# Cymru_55.net
KiCad netlist of a schematic drawn in EAGLE
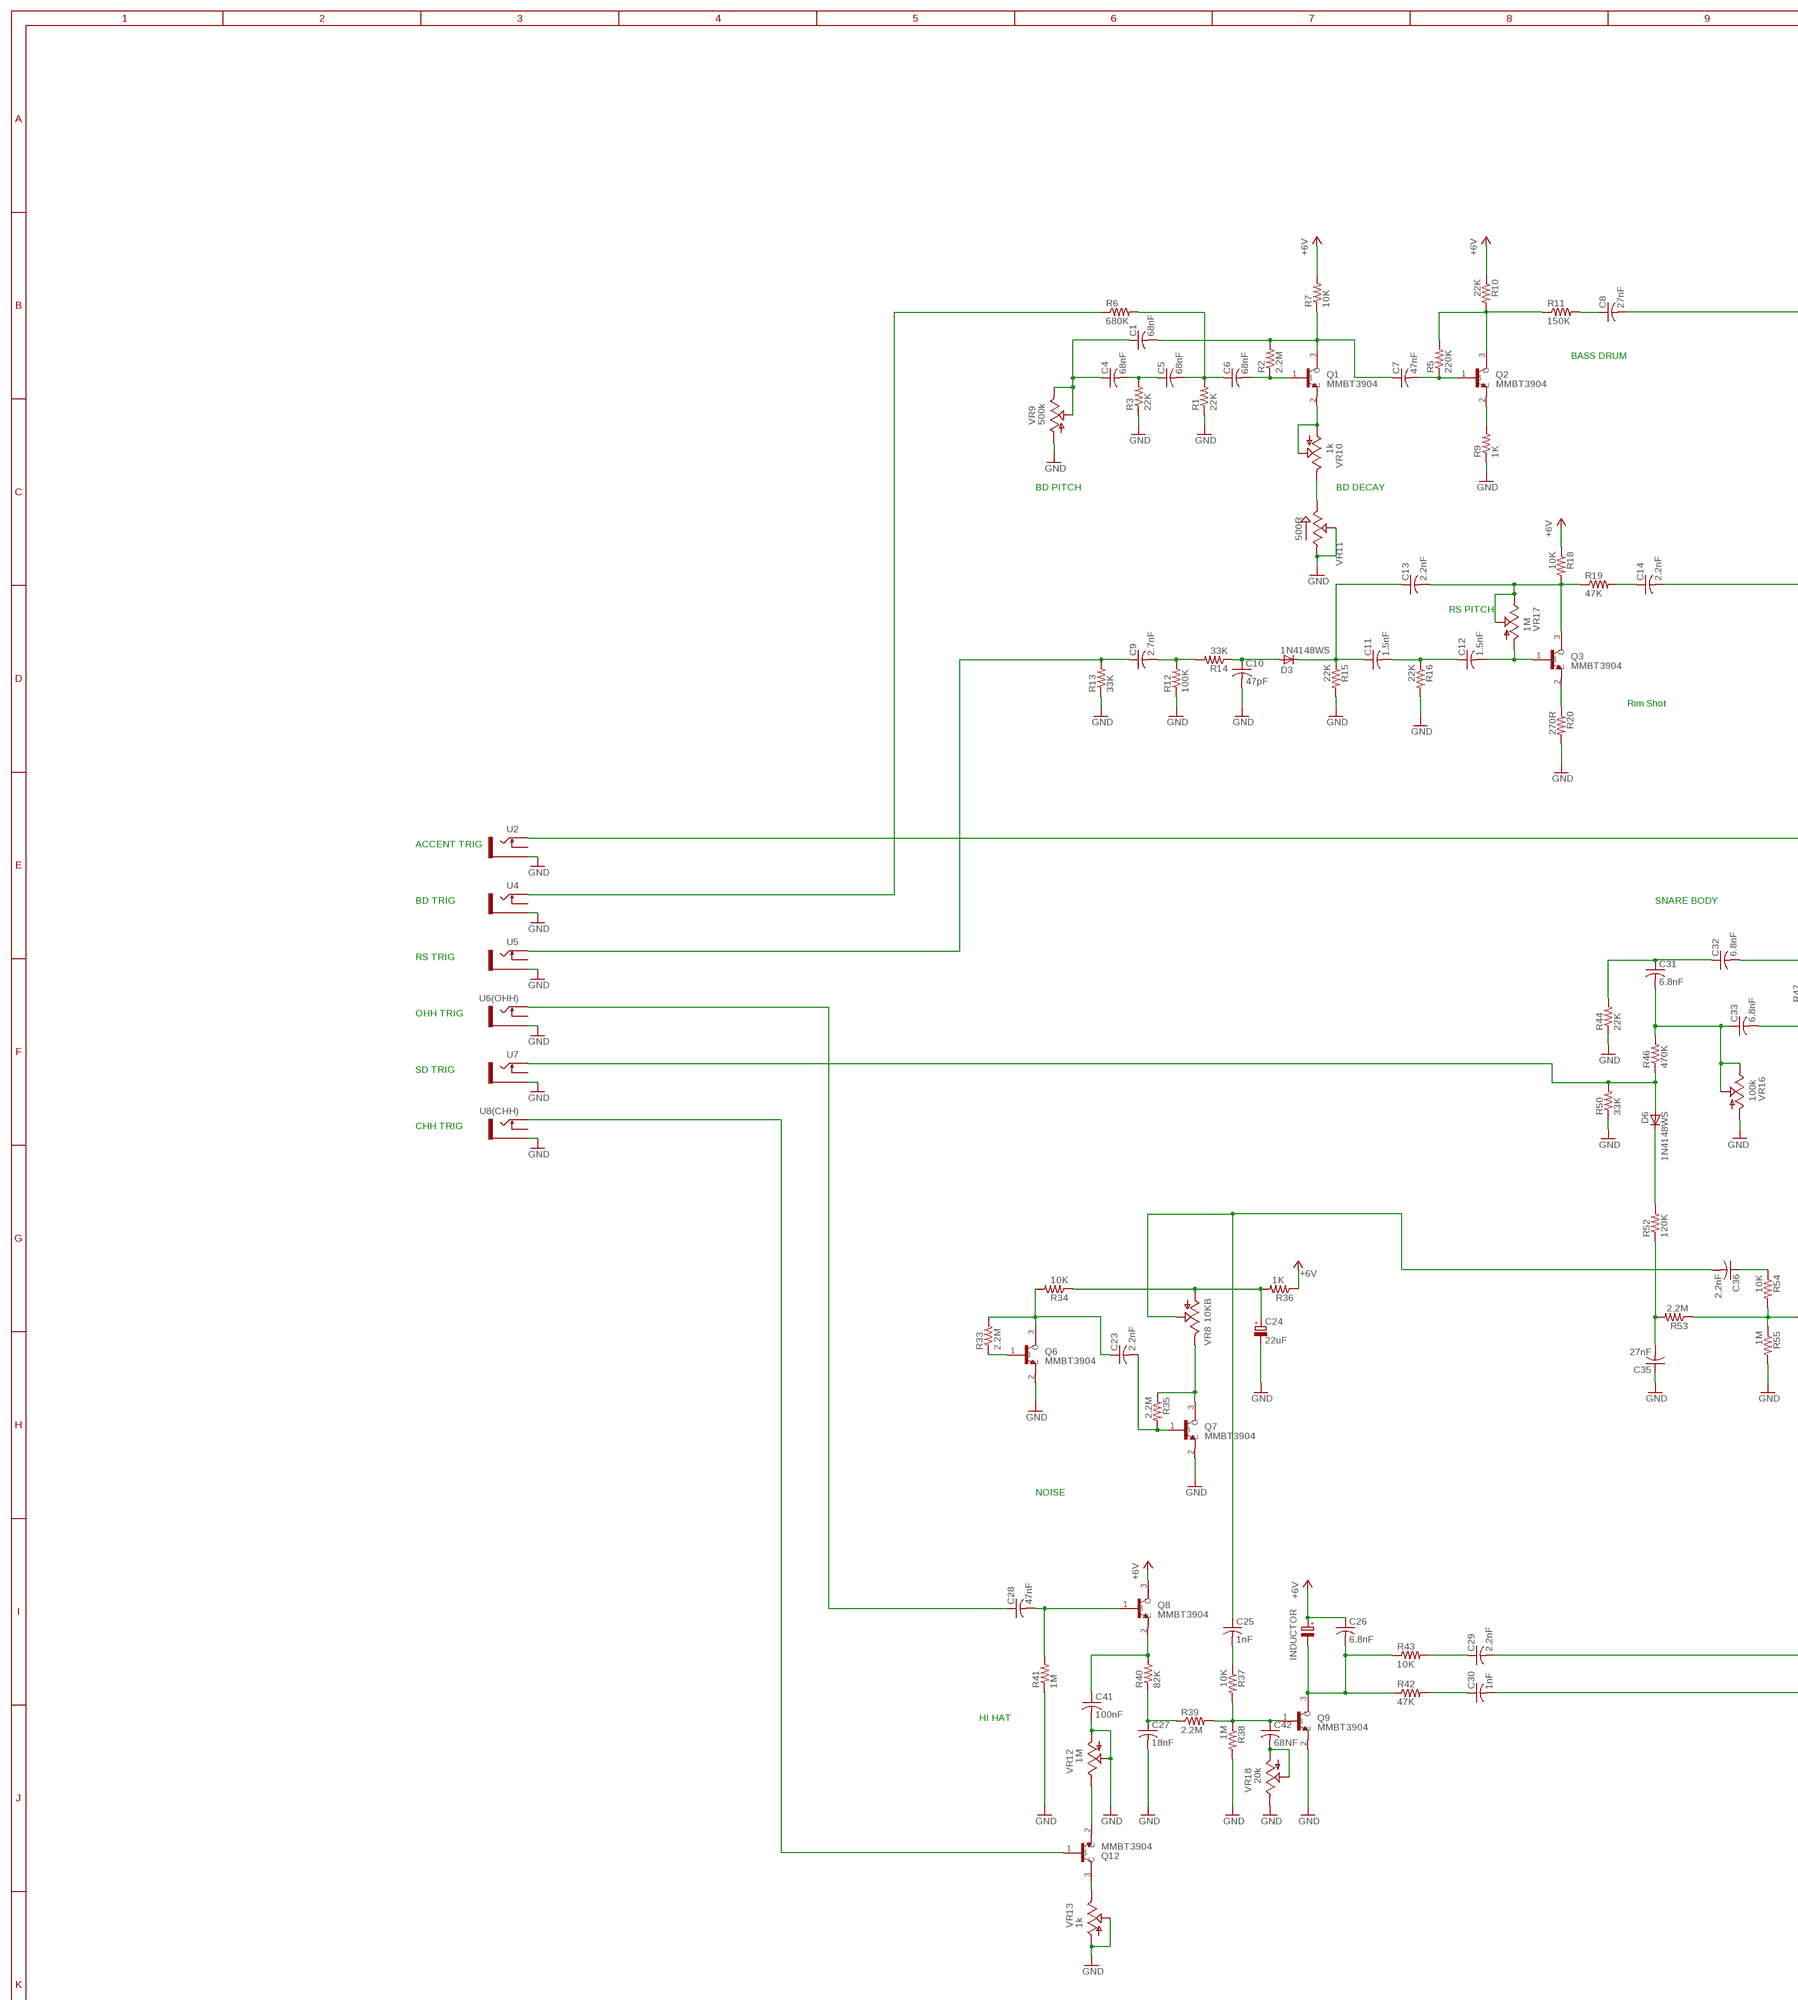
[diagram p0: schematic, sheet 1, part 1 of 3]
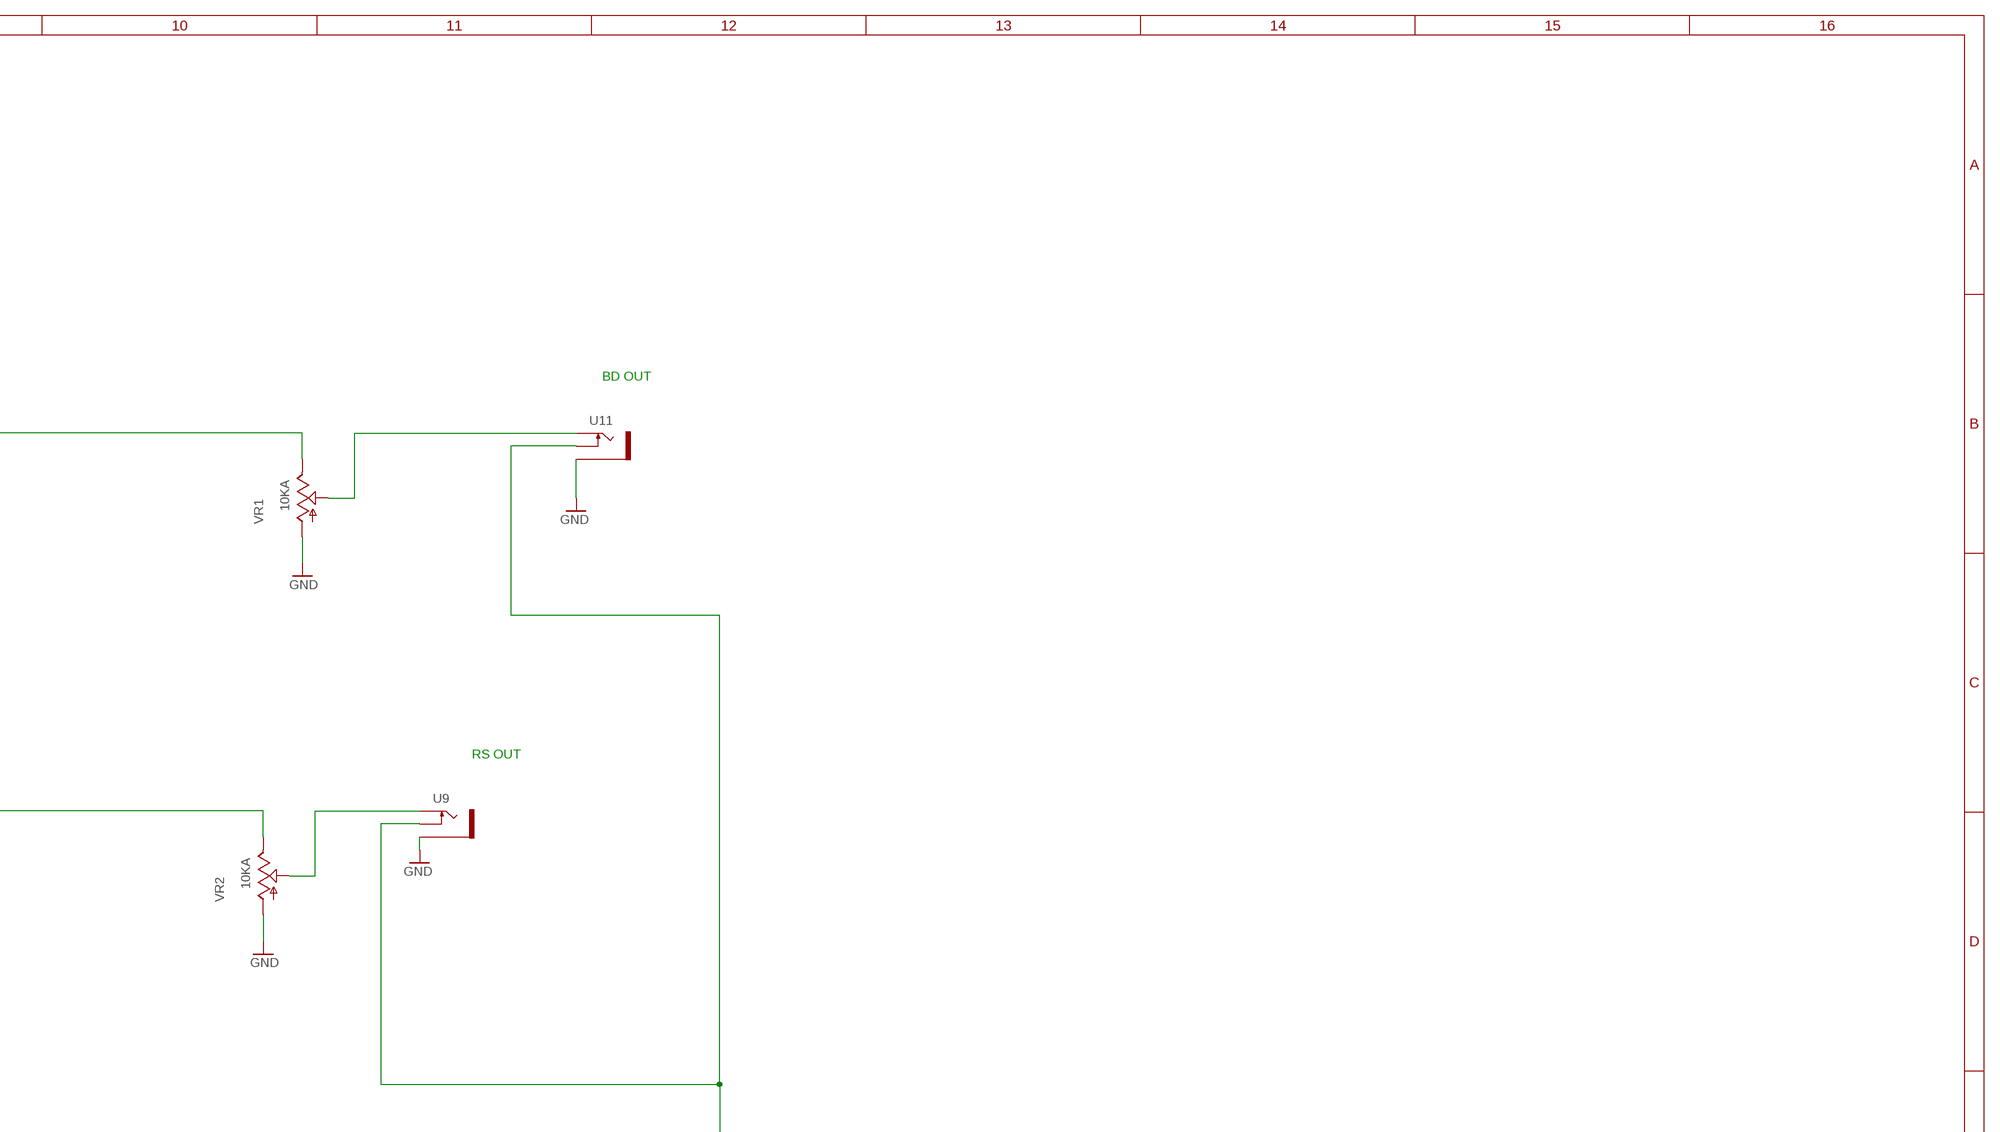
[diagram p1: schematic, sheet 1, part 2 of 3]
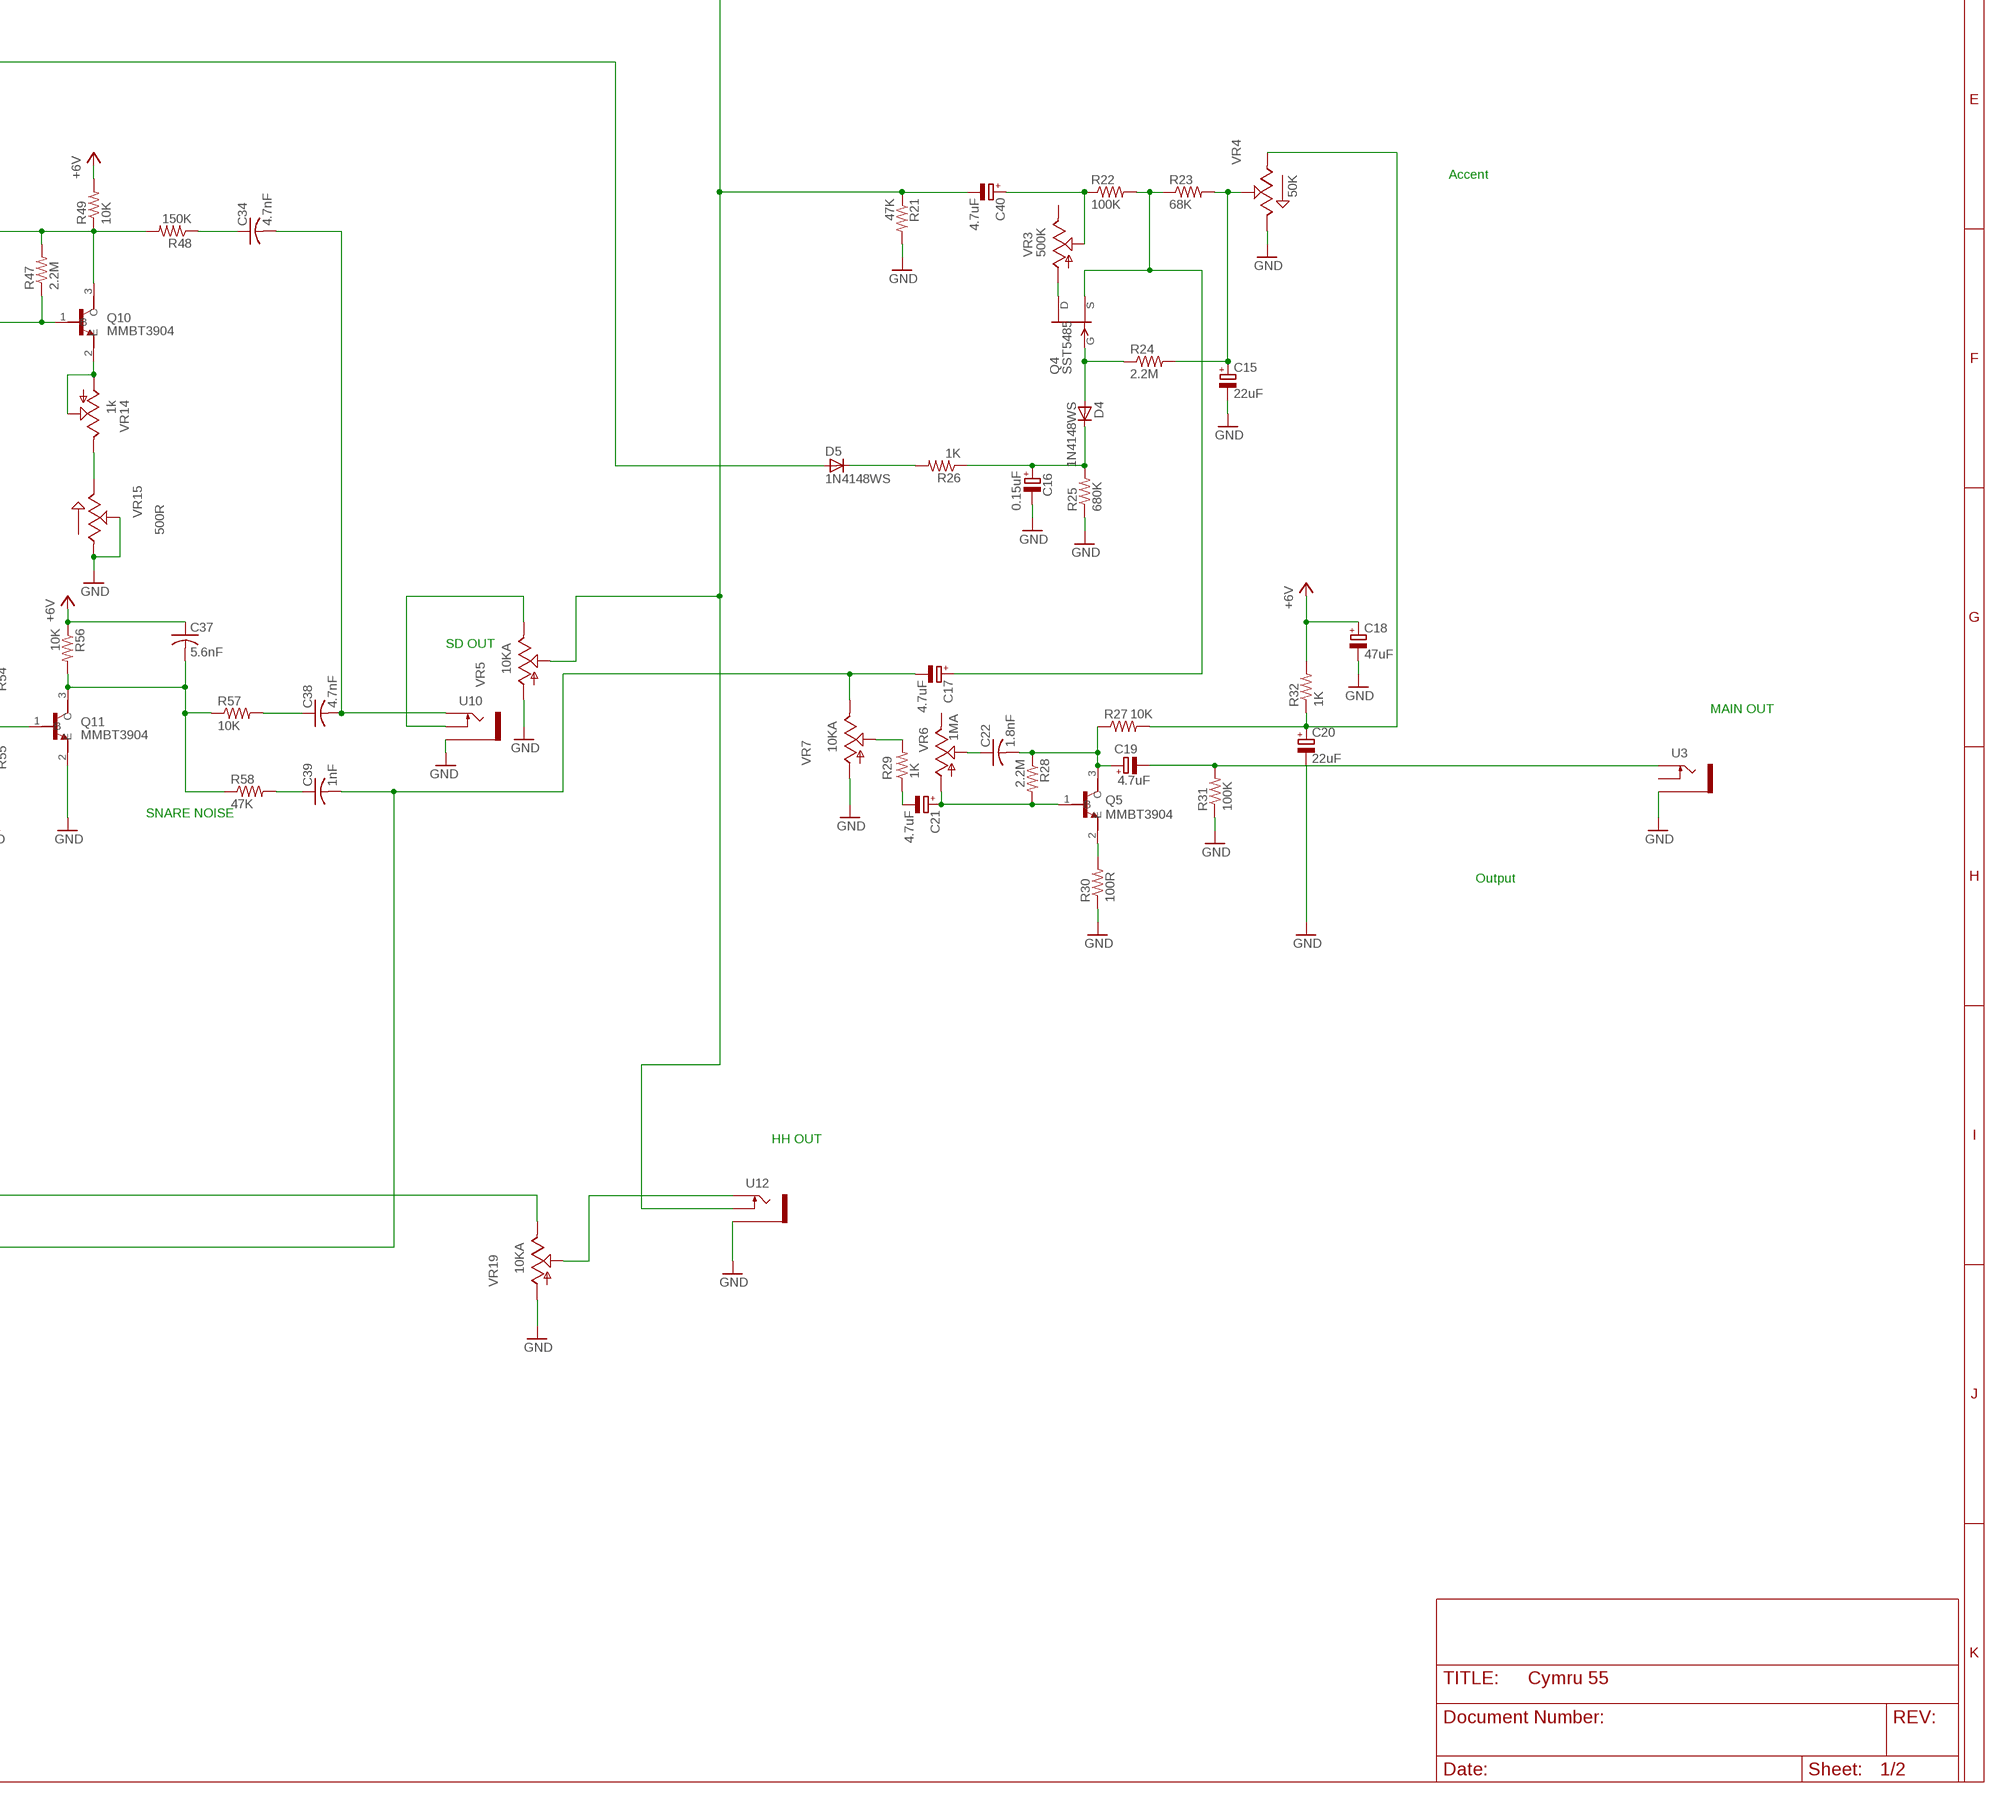
[diagram p2: schematic, sheet 1, part 3 of 3]
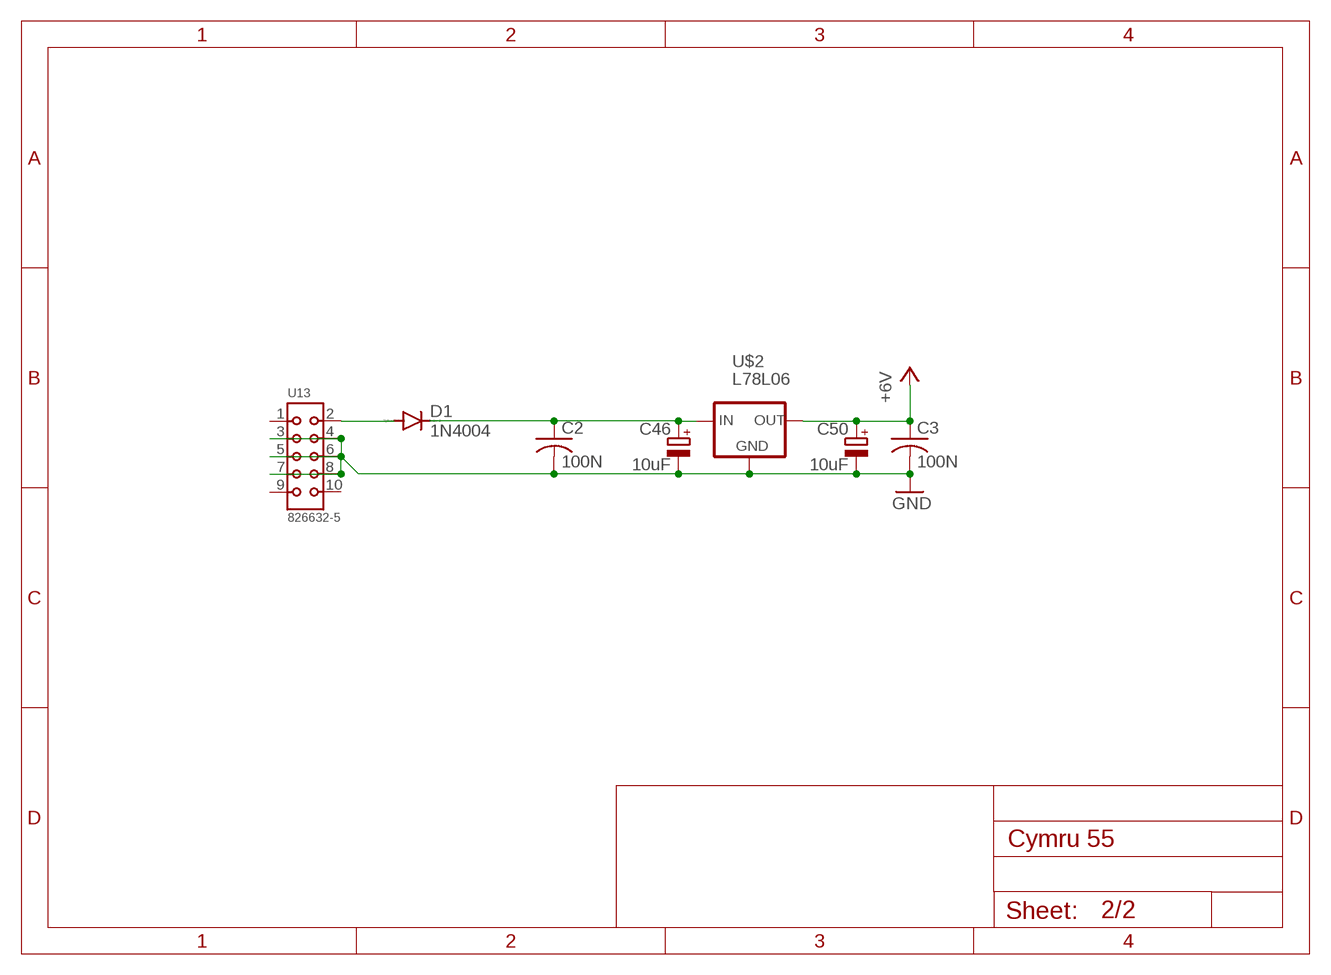
[diagram p3: schematic, sheet 2]

(export (version "E")
  (design (tool "Eeschema 10.0.6"))
  (components
    (comp (ref "C1")
      (value "68nF")
      (footprint "eagle-import:C0603")
      (libsource (lib "eagle-import") (part "C-USC0603"))
    )
    (comp (ref "C4")
      (value "68nF")
      (footprint "eagle-import:C0603")
      (libsource (lib "eagle-import") (part "C-USC0603"))
    )
    (comp (ref "C5")
      (value "68nF")
      (footprint "eagle-import:C0603")
      (libsource (lib "eagle-import") (part "C-USC0603"))
    )
    (comp (ref "C6")
      (value "68nF")
      (footprint "eagle-import:C0603")
      (libsource (lib "eagle-import") (part "C-USC0603"))
    )
    (comp (ref "C7")
      (value "47nF")
      (footprint "eagle-import:C0603")
      (libsource (lib "eagle-import") (part "C-USC0603"))
    )
    (comp (ref "C8")
      (value "27nF")
      (footprint "eagle-import:C0603")
      (libsource (lib "eagle-import") (part "C-USC0603"))
    )
    (comp (ref "C9")
      (value "2.7nF")
      (footprint "eagle-import:C0603")
      (libsource (lib "eagle-import") (part "C-USC0603"))
    )
    (comp (ref "C10")
      (value "47pF")
      (footprint "eagle-import:C0603")
      (libsource (lib "eagle-import") (part "C-USC0603"))
    )
    (comp (ref "C11")
      (value "1.5nF")
      (footprint "eagle-import:C0603")
      (libsource (lib "eagle-import") (part "C-USC0603"))
    )
    (comp (ref "C12")
      (value "1.5nF")
      (footprint "eagle-import:C0603")
      (libsource (lib "eagle-import") (part "C-USC0603"))
    )
    (comp (ref "C13")
      (value "2.2nF")
      (footprint "eagle-import:C0603")
      (libsource (lib "eagle-import") (part "C-USC0603"))
    )
    (comp (ref "C14")
      (value "2.2nF")
      (footprint "eagle-import:C0603")
      (libsource (lib "eagle-import") (part "C-USC0603"))
    )
    (comp (ref "C15")
      (value "22uF")
      (footprint "eagle-import:E2,5RE")
      (libsource (lib "eagle-import") (part "CPOL-EUE2.5-4V"))
    )
    (comp (ref "C16")
      (value "0.15uF")
      (footprint "eagle-import:E2,5RE")
      (libsource (lib "eagle-import") (part "CPOL-EUE2.5-4V"))
    )
    (comp (ref "C17")
      (value "4.7uF")
      (footprint "eagle-import:E2,5RE")
      (libsource (lib "eagle-import") (part "CPOL-EUE2.5-4V"))
    )
    (comp (ref "C18")
      (value "47uF")
      (footprint "eagle-import:E2,5RE")
      (libsource (lib "eagle-import") (part "CPOL-EUE2.5-4V"))
    )
    (comp (ref "C19")
      (value "4.7uF")
      (footprint "eagle-import:E2,5RE")
      (libsource (lib "eagle-import") (part "CPOL-EUE2.5-4V"))
    )
    (comp (ref "C20")
      (value "22uF")
      (footprint "eagle-import:E2,5RE")
      (libsource (lib "eagle-import") (part "CPOL-EUE2.5-4V"))
    )
    (comp (ref "C21")
      (value "4.7uF")
      (footprint "eagle-import:E2,5RE")
      (libsource (lib "eagle-import") (part "CPOL-EUE2.5-4V"))
    )
    (comp (ref "C22")
      (value "1.8nF")
      (footprint "eagle-import:C0603")
      (libsource (lib "eagle-import") (part "C-USC0603"))
    )
    (comp (ref "C23")
      (value "2.2nF")
      (footprint "eagle-import:C0603")
      (libsource (lib "eagle-import") (part "C-USC0603"))
    )
    (comp (ref "C24")
      (value "22uF")
      (footprint "eagle-import:E2,5RE")
      (libsource (lib "eagle-import") (part "CPOL-EUE2.5-4V"))
    )
    (comp (ref "C25")
      (value "1nF")
      (footprint "eagle-import:C0603")
      (libsource (lib "eagle-import") (part "C-USC0603"))
    )
    (comp (ref "C26")
      (value "6.8nF")
      (footprint "eagle-import:C0603")
      (libsource (lib "eagle-import") (part "C-USC0603"))
    )
    (comp (ref "C27")
      (value "18nF")
      (footprint "eagle-import:C0603")
      (libsource (lib "eagle-import") (part "C-USC0603"))
    )
    (comp (ref "C28")
      (value "47nF")
      (footprint "eagle-import:C0603")
      (libsource (lib "eagle-import") (part "C-USC0603"))
    )
    (comp (ref "C29")
      (value "2.2nF")
      (footprint "eagle-import:C0603")
      (libsource (lib "eagle-import") (part "C-USC0603"))
    )
    (comp (ref "C30")
      (value "1nF")
      (footprint "eagle-import:C0603")
      (libsource (lib "eagle-import") (part "C-USC0603"))
    )
    (comp (ref "C31")
      (value "6.8nF")
      (footprint "eagle-import:C0603")
      (libsource (lib "eagle-import") (part "C-USC0603"))
    )
    (comp (ref "C32")
      (value "6.8nF")
      (footprint "eagle-import:C0603")
      (libsource (lib "eagle-import") (part "C-USC0603"))
    )
    (comp (ref "C33")
      (value "6.8nF")
      (footprint "eagle-import:C0603")
      (libsource (lib "eagle-import") (part "C-USC0603"))
    )
    (comp (ref "C34")
      (value "4.7nF")
      (footprint "eagle-import:C0603")
      (libsource (lib "eagle-import") (part "C-USC0603"))
    )
    (comp (ref "C35")
      (value "27nF")
      (footprint "eagle-import:C0603")
      (libsource (lib "eagle-import") (part "C-USC0603"))
    )
    (comp (ref "C36")
      (value "2.2nF")
      (footprint "eagle-import:C0603")
      (libsource (lib "eagle-import") (part "C-USC0603"))
    )
    (comp (ref "C37")
      (value "5.6nF")
      (footprint "eagle-import:C0603")
      (libsource (lib "eagle-import") (part "C-USC0603"))
    )
    (comp (ref "C38")
      (value "4.7nF")
      (footprint "eagle-import:C0603")
      (libsource (lib "eagle-import") (part "C-USC0603"))
    )
    (comp (ref "C39")
      (value "1nF")
      (footprint "eagle-import:C0603")
      (libsource (lib "eagle-import") (part "C-USC0603"))
    )
    (comp (ref "C40")
      (value "4.7uF")
      (footprint "eagle-import:E2,5RE")
      (libsource (lib "eagle-import") (part "CPOL-EUE2.5-4V"))
    )
    (comp (ref "C41")
      (value "100nF")
      (footprint "eagle-import:C0603")
      (libsource (lib "eagle-import") (part "C-USC0603"))
    )
    (comp (ref "C42")
      (value "68NF")
      (footprint "eagle-import:C0603")
      (libsource (lib "eagle-import") (part "C-USC0603"))
    )
    (comp (ref "D3")
      (value "1N4148WS")
      (footprint "eagle-import:SOD323")
      (fields (field (name "MF") "ON Semiconductor"))
      (libsource (lib "eagle-import") (part "1N4148WS"))
    )
    (comp (ref "D4")
      (value "1N4148WS")
      (footprint "eagle-import:SOD323")
      (fields (field (name "MF") "ON Semiconductor"))
      (libsource (lib "eagle-import") (part "1N4148WS"))
    )
    (comp (ref "D5")
      (value "1N4148WS")
      (footprint "eagle-import:SOD323")
      (fields (field (name "MF") "ON Semiconductor"))
      (libsource (lib "eagle-import") (part "1N4148WS"))
    )
    (comp (ref "D6")
      (value "1N4148WS")
      (footprint "eagle-import:SOD323")
      (fields (field (name "MF") "ON Semiconductor"))
      (libsource (lib "eagle-import") (part "1N4148WS"))
    )
    (comp (ref "INDUCTOR")
      (value "47MH")
      (footprint "eagle-import:E2,5RE")
      (libsource (lib "eagle-import") (part "CPOL-EUE2.5-4V"))
    )
    (comp (ref "Q1")
      (value "MMBT3904")
      (footprint "eagle-import:SOT95P240X120-3N")
      (fields (field (name "MF") "STMicroelectronics"))
      (libsource (lib "eagle-import") (part "MMBT3904"))
    )
    (comp (ref "Q2")
      (value "MMBT3904")
      (footprint "eagle-import:SOT95P240X120-3N")
      (fields (field (name "MF") "STMicroelectronics"))
      (libsource (lib "eagle-import") (part "MMBT3904"))
    )
    (comp (ref "Q3")
      (value "MMBT3904")
      (footprint "eagle-import:SOT95P240X120-3N")
      (fields (field (name "MF") "STMicroelectronics"))
      (libsource (lib "eagle-import") (part "MMBT3904"))
    )
    (comp (ref "Q4")
      (value "SST5485")
      (footprint "eagle-import:SOT23")
      (libsource (lib "eagle-import") (part "?548SST5"))
    )
    (comp (ref "Q5")
      (value "MMBT3904")
      (footprint "eagle-import:SOT95P240X120-3N")
      (fields (field (name "MF") "STMicroelectronics"))
      (libsource (lib "eagle-import") (part "MMBT3904"))
    )
    (comp (ref "Q6")
      (value "MMBT3904")
      (footprint "eagle-import:SOT95P240X120-3N")
      (fields (field (name "MF") "STMicroelectronics"))
      (libsource (lib "eagle-import") (part "MMBT3904"))
    )
    (comp (ref "Q7")
      (value "MMBT3904")
      (footprint "eagle-import:SOT95P240X120-3N")
      (fields (field (name "MF") "STMicroelectronics"))
      (libsource (lib "eagle-import") (part "MMBT3904"))
    )
    (comp (ref "Q8")
      (value "MMBT3904")
      (footprint "eagle-import:SOT95P240X120-3N")
      (fields (field (name "MF") "STMicroelectronics"))
      (libsource (lib "eagle-import") (part "MMBT3904"))
    )
    (comp (ref "Q9")
      (value "MMBT3904")
      (footprint "eagle-import:SOT95P240X120-3N")
      (fields (field (name "MF") "STMicroelectronics"))
      (libsource (lib "eagle-import") (part "MMBT3904"))
    )
    (comp (ref "Q10")
      (value "MMBT3904")
      (footprint "eagle-import:SOT95P240X120-3N")
      (fields (field (name "MF") "STMicroelectronics"))
      (libsource (lib "eagle-import") (part "MMBT3904"))
    )
    (comp (ref "Q11")
      (value "MMBT3904")
      (footprint "eagle-import:SOT95P240X120-3N")
      (fields (field (name "MF") "STMicroelectronics"))
      (libsource (lib "eagle-import") (part "MMBT3904"))
    )
    (comp (ref "Q12")
      (value "MMBT3904")
      (footprint "eagle-import:SOT95P240X120-3N")
      (fields (field (name "MF") "STMicroelectronics"))
      (libsource (lib "eagle-import") (part "MMBT3904"))
    )
    (comp (ref "R1")
      (value "22K")
      (footprint "eagle-import:R0603")
      (libsource (lib "eagle-import") (part "R-US_R0603"))
    )
    (comp (ref "R2")
      (value "2.2M")
      (footprint "eagle-import:R0603")
      (libsource (lib "eagle-import") (part "R-US_R0603"))
    )
    (comp (ref "R3")
      (value "22K")
      (footprint "eagle-import:R0603")
      (libsource (lib "eagle-import") (part "R-US_R0603"))
    )
    (comp (ref "R5")
      (value "220K")
      (footprint "eagle-import:R0603")
      (libsource (lib "eagle-import") (part "R-US_R0603"))
    )
    (comp (ref "R6")
      (value "680K")
      (footprint "eagle-import:R0603")
      (libsource (lib "eagle-import") (part "R-US_R0603"))
    )
    (comp (ref "R7")
      (value "10K")
      (footprint "eagle-import:R0603")
      (libsource (lib "eagle-import") (part "R-US_R0603"))
    )
    (comp (ref "R9")
      (value "1K")
      (footprint "eagle-import:R0603")
      (libsource (lib "eagle-import") (part "R-US_R0603"))
    )
    (comp (ref "R10")
      (value "22K")
      (footprint "eagle-import:R0603")
      (libsource (lib "eagle-import") (part "R-US_R0603"))
    )
    (comp (ref "R11")
      (value "150K")
      (footprint "eagle-import:R0603")
      (libsource (lib "eagle-import") (part "R-US_R0603"))
    )
    (comp (ref "R12")
      (value "100K")
      (footprint "eagle-import:R0603")
      (libsource (lib "eagle-import") (part "R-US_R0603"))
    )
    (comp (ref "R13")
      (value "33K")
      (footprint "eagle-import:R0603")
      (libsource (lib "eagle-import") (part "R-US_R0603"))
    )
    (comp (ref "R14")
      (value "33K")
      (footprint "eagle-import:R0603")
      (libsource (lib "eagle-import") (part "R-US_R0603"))
    )
    (comp (ref "R15")
      (value "22K")
      (footprint "eagle-import:R0603")
      (libsource (lib "eagle-import") (part "R-US_R0603"))
    )
    (comp (ref "R16")
      (value "22K")
      (footprint "eagle-import:R0603")
      (libsource (lib "eagle-import") (part "R-US_R0603"))
    )
    (comp (ref "R18")
      (value "10K")
      (footprint "eagle-import:R0603")
      (libsource (lib "eagle-import") (part "R-US_R0603"))
    )
    (comp (ref "R19")
      (value "47K")
      (footprint "eagle-import:R0603")
      (libsource (lib "eagle-import") (part "R-US_R0603"))
    )
    (comp (ref "R20")
      (value "270R")
      (footprint "eagle-import:R0603")
      (libsource (lib "eagle-import") (part "R-US_R0603"))
    )
    (comp (ref "R21")
      (value "47K")
      (footprint "eagle-import:R0603")
      (libsource (lib "eagle-import") (part "R-US_R0603"))
    )
    (comp (ref "R22")
      (value "100K")
      (footprint "eagle-import:R0603")
      (libsource (lib "eagle-import") (part "R-US_R0603"))
    )
    (comp (ref "R23")
      (value "68K")
      (footprint "eagle-import:R0603")
      (libsource (lib "eagle-import") (part "R-US_R0603"))
    )
    (comp (ref "R24")
      (value "2.2M")
      (footprint "eagle-import:R0603")
      (libsource (lib "eagle-import") (part "R-US_R0603"))
    )
    (comp (ref "R25")
      (value "680K")
      (footprint "eagle-import:R0603")
      (libsource (lib "eagle-import") (part "R-US_R0603"))
    )
    (comp (ref "R26")
      (value "1K")
      (footprint "eagle-import:R0603")
      (libsource (lib "eagle-import") (part "R-US_R0603"))
    )
    (comp (ref "R27")
      (value "10K")
      (footprint "eagle-import:R0603")
      (libsource (lib "eagle-import") (part "R-US_R0603"))
    )
    (comp (ref "R28")
      (value "2.2M")
      (footprint "eagle-import:R0603")
      (libsource (lib "eagle-import") (part "R-US_R0603"))
    )
    (comp (ref "R29")
      (value "1K")
      (footprint "eagle-import:R0603")
      (libsource (lib "eagle-import") (part "R-US_R0603"))
    )
    (comp (ref "R30")
      (value "100R")
      (footprint "eagle-import:R0603")
      (libsource (lib "eagle-import") (part "R-US_R0603"))
    )
    (comp (ref "R31")
      (value "100K")
      (footprint "eagle-import:R0603")
      (libsource (lib "eagle-import") (part "R-US_R0603"))
    )
    (comp (ref "R32")
      (value "1K")
      (footprint "eagle-import:R0603")
      (libsource (lib "eagle-import") (part "R-US_R0603"))
    )
    (comp (ref "R33")
      (value "2.2M")
      (footprint "eagle-import:R0603")
      (libsource (lib "eagle-import") (part "R-US_R0603"))
    )
    (comp (ref "R34")
      (value "10K")
      (footprint "eagle-import:R0603")
      (libsource (lib "eagle-import") (part "R-US_R0603"))
    )
    (comp (ref "R35")
      (value "2.2M")
      (footprint "eagle-import:R0603")
      (libsource (lib "eagle-import") (part "R-US_R0603"))
    )
    (comp (ref "R36")
      (value "1K")
      (footprint "eagle-import:R0603")
      (libsource (lib "eagle-import") (part "R-US_R0603"))
    )
    (comp (ref "R37")
      (value "10K")
      (footprint "eagle-import:R0603")
      (libsource (lib "eagle-import") (part "R-US_R0603"))
    )
    (comp (ref "R38")
      (value "1M")
      (footprint "eagle-import:R0603")
      (libsource (lib "eagle-import") (part "R-US_R0603"))
    )
    (comp (ref "R39")
      (value "2.2M")
      (footprint "eagle-import:R0603")
      (libsource (lib "eagle-import") (part "R-US_R0603"))
    )
    (comp (ref "R40")
      (value "82K")
      (footprint "eagle-import:R0603")
      (libsource (lib "eagle-import") (part "R-US_R0603"))
    )
    (comp (ref "R41")
      (value "1M")
      (footprint "eagle-import:R0603")
      (libsource (lib "eagle-import") (part "R-US_R0603"))
    )
    (comp (ref "R42")
      (value "47K")
      (footprint "eagle-import:R0603")
      (libsource (lib "eagle-import") (part "R-US_R0603"))
    )
    (comp (ref "R43")
      (value "10K")
      (footprint "eagle-import:R0603")
      (libsource (lib "eagle-import") (part "R-US_R0603"))
    )
    (comp (ref "R44")
      (value "22K")
      (footprint "eagle-import:R0603")
      (libsource (lib "eagle-import") (part "R-US_R0603"))
    )
    (comp (ref "R46")
      (value "470K")
      (footprint "eagle-import:R0603")
      (libsource (lib "eagle-import") (part "R-US_R0603"))
    )
    (comp (ref "R47")
      (value "2.2M")
      (footprint "eagle-import:R0603")
      (libsource (lib "eagle-import") (part "R-US_R0603"))
    )
    (comp (ref "R48")
      (value "150K")
      (footprint "eagle-import:R0603")
      (libsource (lib "eagle-import") (part "R-US_R0603"))
    )
    (comp (ref "R49")
      (value "10K")
      (footprint "eagle-import:R0603")
      (libsource (lib "eagle-import") (part "R-US_R0603"))
    )
    (comp (ref "R50")
      (value "33K")
      (footprint "eagle-import:R0603")
      (libsource (lib "eagle-import") (part "R-US_R0603"))
    )
    (comp (ref "R52")
      (value "120K")
      (footprint "eagle-import:R0603")
      (libsource (lib "eagle-import") (part "R-US_R0603"))
    )
    (comp (ref "R53")
      (value "2.2M")
      (footprint "eagle-import:R0603")
      (libsource (lib "eagle-import") (part "R-US_R0603"))
    )
    (comp (ref "R54")
      (value "10K")
      (footprint "eagle-import:R0603")
      (libsource (lib "eagle-import") (part "R-US_R0603"))
    )
    (comp (ref "R55")
      (value "1M")
      (footprint "eagle-import:R0603")
      (libsource (lib "eagle-import") (part "R-US_R0603"))
    )
    (comp (ref "R56")
      (value "10K")
      (footprint "eagle-import:R0603")
      (libsource (lib "eagle-import") (part "R-US_R0603"))
    )
    (comp (ref "R57")
      (value "10K")
      (footprint "eagle-import:R0603")
      (libsource (lib "eagle-import") (part "R-US_R0603"))
    )
    (comp (ref "R58")
      (value "47K")
      (footprint "eagle-import:R0603")
      (libsource (lib "eagle-import") (part "R-US_R0603"))
    )
    (comp (ref "U2")
      (value "THONKICONNNEW")
      (footprint "eagle-import:WQP-PJ301M-12_JACK")
      (libsource (lib "eagle-import") (part "THONKICONNNEW"))
    )
    (comp (ref "U3")
      (value "THONKICONNNEW")
      (footprint "eagle-import:WQP-PJ301M-12_JACK")
      (libsource (lib "eagle-import") (part "THONKICONNNEW"))
    )
    (comp (ref "U4")
      (value "THONKICONNNEW")
      (footprint "eagle-import:WQP-PJ301M-12_JACK")
      (libsource (lib "eagle-import") (part "THONKICONNNEW"))
    )
    (comp (ref "U5")
      (value "THONKICONNNEW")
      (footprint "eagle-import:WQP-PJ301M-12_JACK")
      (libsource (lib "eagle-import") (part "THONKICONNNEW"))
    )
    (comp (ref "U6(OHH)")
      (value "THONKICONNNEW")
      (footprint "eagle-import:WQP-PJ301M-12_JACK")
      (libsource (lib "eagle-import") (part "THONKICONNNEW"))
    )
    (comp (ref "U7")
      (value "THONKICONNNEW")
      (footprint "eagle-import:WQP-PJ301M-12_JACK")
      (libsource (lib "eagle-import") (part "THONKICONNNEW"))
    )
    (comp (ref "U8(CHH)")
      (value "THONKICONNNEW")
      (footprint "eagle-import:WQP-PJ301M-12_JACK")
      (libsource (lib "eagle-import") (part "THONKICONNNEW"))
    )
    (comp (ref "U9")
      (value "THONKICONNNEW")
      (footprint "eagle-import:WQP-PJ301M-12_JACK")
      (libsource (lib "eagle-import") (part "THONKICONNNEW"))
    )
    (comp (ref "U10")
      (value "THONKICONNNEW")
      (footprint "eagle-import:WQP-PJ301M-12_JACK")
      (libsource (lib "eagle-import") (part "THONKICONNNEW"))
    )
    (comp (ref "U11")
      (value "THONKICONNNEW")
      (footprint "eagle-import:WQP-PJ301M-12_JACK")
      (libsource (lib "eagle-import") (part "THONKICONNNEW"))
    )
    (comp (ref "U12")
      (value "THONKICONNNEW")
      (footprint "eagle-import:WQP-PJ301M-12_JACK")
      (libsource (lib "eagle-import") (part "THONKICONNNEW"))
    )
    (comp (ref "VR1")
      (value "10KA")
      (footprint "eagle-import:9MM_SNAP-IN_POT")
      (libsource (lib "eagle-import") (part "9MM_SNAP-IN_POT_"))
    )
    (comp (ref "VR2")
      (value "10KA")
      (footprint "eagle-import:9MM_SNAP-IN_POT")
      (libsource (lib "eagle-import") (part "9MM_SNAP-IN_POT_"))
    )
    (comp (ref "VR3")
      (value "500K")
      (footprint "eagle-import:9MM_SNAP-IN_POT")
      (libsource (lib "eagle-import") (part "9MM_SNAP-IN_POT_"))
    )
    (comp (ref "VR4")
      (value "50K")
      (footprint "eagle-import:TRIM_3296W-1-250LF")
      (fields (field (name "MF") "Bourns") (field (name "MP") "3296W-1-250LF"))
      (libsource (lib "eagle-import") (part "3296W-1-250LF"))
    )
    (comp (ref "VR5")
      (value "10KA")
      (footprint "eagle-import:9MM_SNAP-IN_POT")
      (libsource (lib "eagle-import") (part "9MM_SNAP-IN_POT_"))
    )
    (comp (ref "VR6")
      (value "1MA")
      (footprint "eagle-import:9MM_SNAP-IN_POT")
      (libsource (lib "eagle-import") (part "9MM_SNAP-IN_POT_"))
    )
    (comp (ref "VR7")
      (value "10KA")
      (footprint "eagle-import:9MM_SNAP-IN_POT")
      (libsource (lib "eagle-import") (part "9MM_SNAP-IN_POT_"))
    )
    (comp (ref "VR8")
      (value "10KB")
      (footprint "eagle-import:9MM_SNAP-IN_POT")
      (libsource (lib "eagle-import") (part "9MM_SNAP-IN_POT_"))
    )
    (comp (ref "VR9")
      (value "500k")
      (footprint "eagle-import:9MM_SNAP-IN_POT")
      (libsource (lib "eagle-import") (part "9MM_SNAP-IN_POT_"))
    )
    (comp (ref "VR10")
      (value "1k")
      (footprint "eagle-import:9MM_SNAP-IN_POT")
      (libsource (lib "eagle-import") (part "9MM_SNAP-IN_POT_"))
    )
    (comp (ref "VR11")
      (value "500R")
      (footprint "eagle-import:TRIM_3296W-1-250LF")
      (fields (field (name "MF") "Bourns") (field (name "MP") "3296W-1-250LF"))
      (libsource (lib "eagle-import") (part "3296W-1-250LF"))
    )
    (comp (ref "VR12")
      (value "1M")
      (footprint "eagle-import:9MM_SNAP-IN_POT")
      (libsource (lib "eagle-import") (part "9MM_SNAP-IN_POT_"))
    )
    (comp (ref "VR13")
      (value "1k")
      (footprint "eagle-import:9MM_SNAP-IN_POT")
      (libsource (lib "eagle-import") (part "9MM_SNAP-IN_POT_"))
    )
    (comp (ref "VR14")
      (value "1k")
      (footprint "eagle-import:9MM_SNAP-IN_POT")
      (libsource (lib "eagle-import") (part "9MM_SNAP-IN_POT_"))
    )
    (comp (ref "VR15")
      (value "500R")
      (footprint "eagle-import:TRIM_3296W-1-250LF")
      (fields (field (name "MF") "Bourns") (field (name "MP") "3296W-1-250LF"))
      (libsource (lib "eagle-import") (part "3296W-1-250LF"))
    )
    (comp (ref "VR16")
      (value "100k")
      (footprint "eagle-import:9MM_SNAP-IN_POT")
      (libsource (lib "eagle-import") (part "9MM_SNAP-IN_POT_"))
    )
    (comp (ref "VR17")
      (value "1M")
      (footprint "eagle-import:9MM_SNAP-IN_POT")
      (libsource (lib "eagle-import") (part "9MM_SNAP-IN_POT_"))
    )
    (comp (ref "VR18")
      (value "20k")
      (footprint "eagle-import:9MM_SNAP-IN_POT")
      (libsource (lib "eagle-import") (part "9MM_SNAP-IN_POT_"))
    )
    (comp (ref "VR19")
      (value "10KA")
      (footprint "eagle-import:9MM_SNAP-IN_POT")
      (libsource (lib "eagle-import") (part "9MM_SNAP-IN_POT_"))
    )
    (comp (ref "C2")
      (value "100N")
      (footprint "eagle-import:C0603")
      (libsource (lib "eagle-import") (part "C-USC0603"))
    )
    (comp (ref "C3")
      (value "100N")
      (footprint "eagle-import:C0603")
      (libsource (lib "eagle-import") (part "C-USC0603"))
    )
    (comp (ref "C46")
      (value "10uF")
      (footprint "eagle-import:E2,5RE")
      (libsource (lib "eagle-import") (part "CPOL-EUE2.5-4V"))
    )
    (comp (ref "C50")
      (value "10uF")
      (footprint "eagle-import:E2,5RE")
      (libsource (lib "eagle-import") (part "CPOL-EUE2.5-4V"))
    )
    (comp (ref "D1")
      (value "1N4004")
      (footprint "eagle-import:DO41-10")
      (libsource (lib "eagle-import") (part "1N4004"))
    )
    (comp (ref "U$2")
      (value "L78L06")
      (footprint "eagle-import:SOT89")
      (fields (field (name "MF") "STMicroelectronics") (field (name "MP") "L78L05ACU-TR"))
      (libsource (lib "eagle-import") (part "L78L06"))
    )
    (comp (ref "U13")
      (value "826632-5")
      (footprint "eagle-import:HDRV10W63P254_2X5_1270X500X950P")
      (fields (field (name "MF") "TE"))
      (libsource (lib "eagle-import") (part "826632-5"))
    )
  )
  (nets
    (net (code "1") (name "+5V") (class "Default")
      (node (ref "C18") (pin "+") (pinfunction "+_+") (pintype "passive"))
      (node (ref "C26") (pin "1") (pinfunction "1_1") (pintype "passive"))
      (node (ref "C3") (pin "1") (pinfunction "1_1") (pintype "passive"))
      (node (ref "C37") (pin "1") (pinfunction "1_1") (pintype "passive"))
      (node (ref "C50") (pin "+") (pinfunction "+_+") (pintype "passive"))
      (node (ref "INDUCTOR") (pin "+") (pinfunction "+_+") (pintype "passive"))
      (node (ref "Q8") (pin "3") (pinfunction "C_3") (pintype "passive"))
      (node (ref "R10") (pin "1") (pinfunction "1_1") (pintype "passive"))
      (node (ref "R18") (pin "1") (pinfunction "1_1") (pintype "passive"))
      (node (ref "R32") (pin "2") (pinfunction "2_2") (pintype "passive"))
      (node (ref "R36") (pin "1") (pinfunction "1_1") (pintype "passive"))
      (node (ref "R49") (pin "2") (pinfunction "2_2") (pintype "passive"))
      (node (ref "R56") (pin "1") (pinfunction "1_1") (pintype "passive"))
      (node (ref "R7") (pin "2") (pinfunction "2_2") (pintype "passive"))
      (node (ref "U$2") (pin "1") (pinfunction "OUT_1") (pintype "output"))
    )
    (net (code "2") (name "GND") (class "Default")
      (node (ref "C10") (pin "2") (pinfunction "2_2") (pintype "passive"))
      (node (ref "C15") (pin "-") (pinfunction "-_-") (pintype "passive"))
      (node (ref "C16") (pin "-") (pinfunction "-_-") (pintype "passive"))
      (node (ref "C18") (pin "-") (pinfunction "-_-") (pintype "passive"))
      (node (ref "C2") (pin "2") (pinfunction "2_2") (pintype "passive"))
      (node (ref "C20") (pin "-") (pinfunction "-_-") (pintype "passive"))
      (node (ref "C24") (pin "-") (pinfunction "-_-") (pintype "passive"))
      (node (ref "C27") (pin "2") (pinfunction "2_2") (pintype "passive"))
      (node (ref "C3") (pin "2") (pinfunction "2_2") (pintype "passive"))
      (node (ref "C35") (pin "1") (pinfunction "1_1") (pintype "passive"))
      (node (ref "C41") (pin "2") (pinfunction "2_2") (pintype "passive"))
      (node (ref "C46") (pin "-") (pinfunction "-_-") (pintype "passive"))
      (node (ref "C50") (pin "-") (pinfunction "-_-") (pintype "passive"))
      (node (ref "Q11") (pin "2") (pinfunction "E_2") (pintype "passive"))
      (node (ref "Q6") (pin "2") (pinfunction "E_2") (pintype "passive"))
      (node (ref "Q7") (pin "2") (pinfunction "E_2") (pintype "passive"))
      (node (ref "Q9") (pin "2") (pinfunction "E_2") (pintype "passive"))
      (node (ref "R1") (pin "1") (pinfunction "1_1") (pintype "passive"))
      (node (ref "R12") (pin "1") (pinfunction "1_1") (pintype "passive"))
      (node (ref "R13") (pin "1") (pinfunction "1_1") (pintype "passive"))
      (node (ref "R15") (pin "2") (pinfunction "2_2") (pintype "passive"))
      (node (ref "R16") (pin "2") (pinfunction "2_2") (pintype "passive"))
      (node (ref "R20") (pin "2") (pinfunction "2_2") (pintype "passive"))
      (node (ref "R21") (pin "2") (pinfunction "2_2") (pintype "passive"))
      (node (ref "R25") (pin "1") (pinfunction "1_1") (pintype "passive"))
      (node (ref "R3") (pin "1") (pinfunction "1_1") (pintype "passive"))
      (node (ref "R30") (pin "1") (pinfunction "1_1") (pintype "passive"))
      (node (ref "R31") (pin "1") (pinfunction "1_1") (pintype "passive"))
      (node (ref "R38") (pin "2") (pinfunction "2_2") (pintype "passive"))
      (node (ref "R41") (pin "1") (pinfunction "1_1") (pintype "passive"))
      (node (ref "R44") (pin "1") (pinfunction "1_1") (pintype "passive"))
      (node (ref "R50") (pin "1") (pinfunction "1_1") (pintype "passive"))
      (node (ref "R55") (pin "2") (pinfunction "2_2") (pintype "passive"))
      (node (ref "R9") (pin "1") (pinfunction "1_1") (pintype "passive"))
      (node (ref "U$2") (pin "2") (pinfunction "GND_2") (pintype "input"))
      (node (ref "U10") (pin "P$3_SLEEVE") (pinfunction "SLEEVE_P$3_SLEEVE") (pintype "passive"))
      (node (ref "U11") (pin "P$3_SLEEVE") (pinfunction "SLEEVE_P$3_SLEEVE") (pintype "passive"))
      (node (ref "U12") (pin "P$3_SLEEVE") (pinfunction "SLEEVE_P$3_SLEEVE") (pintype "passive"))
      (node (ref "U13") (pin "3") (pinfunction "3_3") (pintype "passive"))
      (node (ref "U13") (pin "4") (pinfunction "4_4") (pintype "passive"))
      (node (ref "U13") (pin "5") (pinfunction "5_5") (pintype "passive"))
      (node (ref "U13") (pin "6") (pinfunction "6_6") (pintype "passive"))
      (node (ref "U13") (pin "7") (pinfunction "7_7") (pintype "passive"))
      (node (ref "U13") (pin "8") (pinfunction "8_8") (pintype "passive"))
      (node (ref "U2") (pin "P$3_SLEEVE") (pinfunction "SLEEVE_P$3_SLEEVE") (pintype "passive"))
      (node (ref "U3") (pin "P$3_SLEEVE") (pinfunction "SLEEVE_P$3_SLEEVE") (pintype "passive"))
      (node (ref "U4") (pin "P$3_SLEEVE") (pinfunction "SLEEVE_P$3_SLEEVE") (pintype "passive"))
      (node (ref "U5") (pin "P$3_SLEEVE") (pinfunction "SLEEVE_P$3_SLEEVE") (pintype "passive"))
      (node (ref "U6(OHH)") (pin "P$3_SLEEVE") (pinfunction "SLEEVE_P$3_SLEEVE") (pintype "passive"))
      (node (ref "U7") (pin "P$3_SLEEVE") (pinfunction "SLEEVE_P$3_SLEEVE") (pintype "passive"))
      (node (ref "U8(CHH)") (pin "P$3_SLEEVE") (pinfunction "SLEEVE_P$3_SLEEVE") (pintype "passive"))
      (node (ref "U9") (pin "P$3_SLEEVE") (pinfunction "SLEEVE_P$3_SLEEVE") (pintype "passive"))
      (node (ref "VR1") (pin "1") (pinfunction "A_1") (pintype "passive"))
      (node (ref "VR11") (pin "1") (pinfunction "CCW_1") (pintype "passive"))
      (node (ref "VR11") (pin "2") (pinfunction "WIPER_2") (pintype "passive"))
      (node (ref "VR12") (pin "1") (pinfunction "A_1") (pintype "passive"))
      (node (ref "VR12") (pin "2") (pinfunction "S_2") (pintype "passive"))
      (node (ref "VR13") (pin "1") (pinfunction "A_1") (pintype "passive"))
      (node (ref "VR13") (pin "2") (pinfunction "S_2") (pintype "passive"))
      (node (ref "VR15") (pin "1") (pinfunction "CCW_1") (pintype "passive"))
      (node (ref "VR15") (pin "2") (pinfunction "WIPER_2") (pintype "passive"))
      (node (ref "VR16") (pin "1") (pinfunction "A_1") (pintype "passive"))
      (node (ref "VR18") (pin "3") (pinfunction "E_3") (pintype "passive"))
      (node (ref "VR19") (pin "1") (pinfunction "A_1") (pintype "passive"))
      (node (ref "VR2") (pin "1") (pinfunction "A_1") (pintype "passive"))
      (node (ref "VR4") (pin "3") (pinfunction "CW_3") (pintype "passive"))
      (node (ref "VR5") (pin "1") (pinfunction "A_1") (pintype "passive"))
      (node (ref "VR7") (pin "1") (pinfunction "A_1") (pintype "passive"))
      (node (ref "VR9") (pin "1") (pinfunction "A_1") (pintype "passive"))
    )
    (net (code "3") (name "Net-(C4-Pad2)") (class "Default")
      (node (ref "C4") (pin "2") (pinfunction "2_2") (pintype "passive"))
      (node (ref "C5") (pin "1") (pinfunction "1_1") (pintype "passive"))
      (node (ref "R3") (pin "2") (pinfunction "2_2") (pintype "passive"))
    )
    (net (code "4") (name "Net-(C5-Pad2)") (class "Default")
      (node (ref "C5") (pin "2") (pinfunction "2_2") (pintype "passive"))
      (node (ref "C6") (pin "1") (pinfunction "1_1") (pintype "passive"))
      (node (ref "R1") (pin "2") (pinfunction "2_2") (pintype "passive"))
      (node (ref "R6") (pin "2") (pinfunction "2_2") (pintype "passive"))
    )
    (net (code "5") (name "Net-(C8-Pad1)") (class "Default")
      (node (ref "C8") (pin "1") (pinfunction "1_1") (pintype "passive"))
      (node (ref "R11") (pin "2") (pinfunction "2_2") (pintype "passive"))
    )
    (net (code "6") (name "Net-(C9-Pad2)") (class "Default")
      (node (ref "C9") (pin "2") (pinfunction "2_2") (pintype "passive"))
      (node (ref "R12") (pin "2") (pinfunction "2_2") (pintype "passive"))
      (node (ref "R14") (pin "2") (pinfunction "2_2") (pintype "passive"))
    )
    (net (code "7") (name "Net-(C10-Pad1)") (class "Default")
      (node (ref "C10") (pin "1") (pinfunction "1_1") (pintype "passive"))
      (node (ref "D3") (pin "A") (pinfunction "A_A") (pintype "passive"))
      (node (ref "R14") (pin "1") (pinfunction "1_1") (pintype "passive"))
    )
    (net (code "8") (name "Net-(C11-Pad1)") (class "Default")
      (node (ref "C11") (pin "1") (pinfunction "1_1") (pintype "passive"))
      (node (ref "C13") (pin "1") (pinfunction "1_1") (pintype "passive"))
      (node (ref "D3") (pin "C") (pinfunction "C_C") (pintype "passive"))
      (node (ref "R15") (pin "1") (pinfunction "1_1") (pintype "passive"))
    )
    (net (code "9") (name "Net-(C11-Pad2)") (class "Default")
      (node (ref "C11") (pin "2") (pinfunction "2_2") (pintype "passive"))
      (node (ref "C12") (pin "1") (pinfunction "1_1") (pintype "passive"))
      (node (ref "R16") (pin "1") (pinfunction "1_1") (pintype "passive"))
    )
    (net (code "10") (name "Net-(C14-Pad1)") (class "Default")
      (node (ref "C14") (pin "1") (pinfunction "1_1") (pintype "passive"))
      (node (ref "R19") (pin "2") (pinfunction "2_2") (pintype "passive"))
    )
    (net (code "11") (name "Net-(C16-Pad+)") (class "Default")
      (node (ref "C16") (pin "+") (pinfunction "+_+") (pintype "passive"))
      (node (ref "D4") (pin "C") (pinfunction "C_C") (pintype "passive"))
      (node (ref "R25") (pin "2") (pinfunction "2_2") (pintype "passive"))
      (node (ref "R26") (pin "1") (pinfunction "1_1") (pintype "passive"))
    )
    (net (code "12") (name "Net-(C21-Pad-)") (class "Default")
      (node (ref "C21") (pin "-") (pinfunction "-_-") (pintype "passive"))
      (node (ref "R29") (pin "1") (pinfunction "1_1") (pintype "passive"))
    )
    (net (code "13") (name "Net-(C25-Pad2)") (class "Default")
      (node (ref "C25") (pin "2") (pinfunction "2_2") (pintype "passive"))
      (node (ref "R37") (pin "1") (pinfunction "1_1") (pintype "passive"))
    )
    (net (code "14") (name "Net-(C27-Pad1)") (class "Default")
      (node (ref "C27") (pin "1") (pinfunction "1_1") (pintype "passive"))
      (node (ref "R39") (pin "1") (pinfunction "1_1") (pintype "passive"))
      (node (ref "R40") (pin "1") (pinfunction "1_1") (pintype "passive"))
    )
    (net (code "15") (name "Net-(C29-Pad1)") (class "Default")
      (node (ref "C29") (pin "1") (pinfunction "1_1") (pintype "passive"))
      (node (ref "R43") (pin "2") (pinfunction "2_2") (pintype "passive"))
    )
    (net (code "16") (name "Net-(C30-Pad1)") (class "Default")
      (node (ref "C30") (pin "1") (pinfunction "1_1") (pintype "passive"))
      (node (ref "R42") (pin "2") (pinfunction "2_2") (pintype "passive"))
    )
    (net (code "17") (name "Net-(C31-Pad1)") (class "Default")
      (node (ref "C31") (pin "1") (pinfunction "1_1") (pintype "passive"))
      (node (ref "C32") (pin "1") (pinfunction "1_1") (pintype "passive"))
      (node (ref "R44") (pin "2") (pinfunction "2_2") (pintype "passive"))
    )
    (net (code "18") (name "Net-(C34-Pad1)") (class "Default")
      (node (ref "C34") (pin "1") (pinfunction "1_1") (pintype "passive"))
      (node (ref "R48") (pin "1") (pinfunction "1_1") (pintype "passive"))
    )
    (net (code "19") (name "Net-(C35-Pad2)") (class "Default")
      (node (ref "C35") (pin "2") (pinfunction "2_2") (pintype "passive"))
      (node (ref "R52") (pin "1") (pinfunction "1_1") (pintype "passive"))
      (node (ref "R53") (pin "2") (pinfunction "2_2") (pintype "passive"))
    )
    (net (code "20") (name "Net-(C36-Pad1)") (class "Default")
      (node (ref "C36") (pin "1") (pinfunction "1_1") (pintype "passive"))
      (node (ref "R54") (pin "1") (pinfunction "1_1") (pintype "passive"))
    )
    (net (code "21") (name "Net-(C38-Pad1)") (class "Default")
      (node (ref "C38") (pin "1") (pinfunction "1_1") (pintype "passive"))
      (node (ref "R57") (pin "2") (pinfunction "2_2") (pintype "passive"))
    )
    (net (code "22") (name "Net-(C39-Pad1)") (class "Default")
      (node (ref "C39") (pin "1") (pinfunction "1_1") (pintype "passive"))
      (node (ref "R58") (pin "2") (pinfunction "2_2") (pintype "passive"))
    )
    (net (code "23") (name "Net-(D1-PadA)") (class "Default")
      (node (ref "D1") (pin "A") (pinfunction "A_A") (pintype "passive"))
      (node (ref "U13") (pin "2") (pinfunction "2_2") (pintype "passive"))
    )
    (net (code "24") (name "Net-(D5-PadC)") (class "Default")
      (node (ref "D5") (pin "C") (pinfunction "C_C") (pintype "passive"))
      (node (ref "R26") (pin "2") (pinfunction "2_2") (pintype "passive"))
    )
    (net (code "25") (name "Net-(D6-PadC)") (class "Default")
      (node (ref "D6") (pin "C") (pinfunction "C_C") (pintype "passive"))
      (node (ref "R52") (pin "2") (pinfunction "2_2") (pintype "passive"))
    )
    (net (code "26") (name "Net-(Q1-B)") (class "Default")
      (node (ref "C6") (pin "2") (pinfunction "2_2") (pintype "passive"))
      (node (ref "Q1") (pin "1") (pinfunction "B_1") (pintype "passive"))
      (node (ref "R2") (pin "1") (pinfunction "1_1") (pintype "passive"))
    )
    (net (code "27") (name "Net-(Q1-C)") (class "Default")
      (node (ref "C1") (pin "2") (pinfunction "2_2") (pintype "passive"))
      (node (ref "C7") (pin "1") (pinfunction "1_1") (pintype "passive"))
      (node (ref "Q1") (pin "3") (pinfunction "C_3") (pintype "passive"))
      (node (ref "R2") (pin "2") (pinfunction "2_2") (pintype "passive"))
      (node (ref "R7") (pin "1") (pinfunction "1_1") (pintype "passive"))
    )
    (net (code "28") (name "Net-(Q1-E)") (class "Default")
      (node (ref "Q1") (pin "2") (pinfunction "E_2") (pintype "passive"))
      (node (ref "VR10") (pin "1") (pinfunction "A_1") (pintype "passive"))
      (node (ref "VR10") (pin "2") (pinfunction "S_2") (pintype "passive"))
    )
    (net (code "29") (name "Net-(Q2-B)") (class "Default")
      (node (ref "C7") (pin "2") (pinfunction "2_2") (pintype "passive"))
      (node (ref "Q2") (pin "1") (pinfunction "B_1") (pintype "passive"))
      (node (ref "R5") (pin "1") (pinfunction "1_1") (pintype "passive"))
    )
    (net (code "30") (name "Net-(Q2-C)") (class "Default")
      (node (ref "Q2") (pin "3") (pinfunction "C_3") (pintype "passive"))
      (node (ref "R10") (pin "2") (pinfunction "2_2") (pintype "passive"))
      (node (ref "R11") (pin "1") (pinfunction "1_1") (pintype "passive"))
      (node (ref "R5") (pin "2") (pinfunction "2_2") (pintype "passive"))
    )
    (net (code "31") (name "Net-(Q2-E)") (class "Default")
      (node (ref "Q2") (pin "2") (pinfunction "E_2") (pintype "passive"))
      (node (ref "R9") (pin "2") (pinfunction "2_2") (pintype "passive"))
    )
    (net (code "32") (name "Net-(Q3-B)") (class "Default")
      (node (ref "C12") (pin "2") (pinfunction "2_2") (pintype "passive"))
      (node (ref "Q3") (pin "1") (pinfunction "B_1") (pintype "passive"))
      (node (ref "VR17") (pin "1") (pinfunction "A_1") (pintype "passive"))
    )
    (net (code "33") (name "Net-(Q3-C)") (class "Default")
      (node (ref "C13") (pin "2") (pinfunction "2_2") (pintype "passive"))
      (node (ref "Q3") (pin "3") (pinfunction "C_3") (pintype "passive"))
      (node (ref "R18") (pin "2") (pinfunction "2_2") (pintype "passive"))
      (node (ref "R19") (pin "1") (pinfunction "1_1") (pintype "passive"))
      (node (ref "VR17") (pin "2") (pinfunction "S_2") (pintype "passive"))
      (node (ref "VR17") (pin "3") (pinfunction "E_3") (pintype "passive"))
    )
    (net (code "34") (name "Net-(Q3-E)") (class "Default")
      (node (ref "Q3") (pin "2") (pinfunction "E_2") (pintype "passive"))
      (node (ref "R20") (pin "1") (pinfunction "1_1") (pintype "passive"))
    )
    (net (code "35") (name "Net-(Q4-D)") (class "Default")
      (node (ref "Q4") (pin "1") (pinfunction "D_1") (pintype "passive"))
      (node (ref "VR3") (pin "1") (pinfunction "A_1") (pintype "passive"))
    )
    (net (code "36") (name "Net-(Q4-G)") (class "Default")
      (node (ref "D4") (pin "A") (pinfunction "A_A") (pintype "passive"))
      (node (ref "Q4") (pin "3") (pinfunction "G_3") (pintype "passive"))
      (node (ref "R24") (pin "1") (pinfunction "1_1") (pintype "passive"))
    )
    (net (code "37") (name "Net-(Q4-S)") (class "Default")
      (node (ref "C17") (pin "+") (pinfunction "+_+") (pintype "passive"))
      (node (ref "Q4") (pin "2") (pinfunction "S_2") (pintype "passive"))
      (node (ref "R22") (pin "2") (pinfunction "2_2") (pintype "passive"))
      (node (ref "R23") (pin "1") (pinfunction "1_1") (pintype "passive"))
    )
    (net (code "38") (name "Net-(Q5-B)") (class "Default")
      (node (ref "C21") (pin "+") (pinfunction "+_+") (pintype "passive"))
      (node (ref "Q5") (pin "1") (pinfunction "B_1") (pintype "passive"))
      (node (ref "R28") (pin "2") (pinfunction "2_2") (pintype "passive"))
      (node (ref "VR6") (pin "1") (pinfunction "A_1") (pintype "passive"))
    )
    (net (code "39") (name "Net-(Q5-C)") (class "Default")
      (node (ref "C19") (pin "+") (pinfunction "+_+") (pintype "passive"))
      (node (ref "C22") (pin "2") (pinfunction "2_2") (pintype "passive"))
      (node (ref "Q5") (pin "3") (pinfunction "C_3") (pintype "passive"))
      (node (ref "R27") (pin "1") (pinfunction "1_1") (pintype "passive"))
      (node (ref "R28") (pin "1") (pinfunction "1_1") (pintype "passive"))
    )
    (net (code "40") (name "Net-(Q5-E)") (class "Default")
      (node (ref "Q5") (pin "2") (pinfunction "E_2") (pintype "passive"))
      (node (ref "R30") (pin "2") (pinfunction "2_2") (pintype "passive"))
    )
    (net (code "41") (name "Net-(Q6-B)") (class "Default")
      (node (ref "Q6") (pin "1") (pinfunction "B_1") (pintype "passive"))
      (node (ref "R33") (pin "1") (pinfunction "1_1") (pintype "passive"))
    )
    (net (code "42") (name "Net-(Q6-C)") (class "Default")
      (node (ref "C23") (pin "1") (pinfunction "1_1") (pintype "passive"))
      (node (ref "Q6") (pin "3") (pinfunction "C_3") (pintype "passive"))
      (node (ref "R33") (pin "2") (pinfunction "2_2") (pintype "passive"))
      (node (ref "R34") (pin "2") (pinfunction "2_2") (pintype "passive"))
    )
    (net (code "43") (name "Net-(Q7-B)") (class "Default")
      (node (ref "C23") (pin "2") (pinfunction "2_2") (pintype "passive"))
      (node (ref "Q7") (pin "1") (pinfunction "B_1") (pintype "passive"))
      (node (ref "R35") (pin "2") (pinfunction "2_2") (pintype "passive"))
    )
    (net (code "44") (name "Net-(Q7-C)") (class "Default")
      (node (ref "Q7") (pin "3") (pinfunction "C_3") (pintype "passive"))
      (node (ref "R35") (pin "1") (pinfunction "1_1") (pintype "passive"))
      (node (ref "VR8") (pin "3") (pinfunction "E_3") (pintype "passive"))
    )
    (net (code "45") (name "Net-(Q8-B)") (class "Default")
      (node (ref "C28") (pin "2") (pinfunction "2_2") (pintype "passive"))
      (node (ref "Q8") (pin "1") (pinfunction "B_1") (pintype "passive"))
      (node (ref "R41") (pin "2") (pinfunction "2_2") (pintype "passive"))
    )
    (net (code "46") (name "Net-(Q8-E)") (class "Default")
      (node (ref "C41") (pin "1") (pinfunction "1_1") (pintype "passive"))
      (node (ref "Q8") (pin "2") (pinfunction "E_2") (pintype "passive"))
      (node (ref "R40") (pin "2") (pinfunction "2_2") (pintype "passive"))
    )
    (net (code "47") (name "Net-(Q9-B)") (class "Default")
      (node (ref "C42") (pin "1") (pinfunction "1_1") (pintype "passive"))
      (node (ref "Q9") (pin "1") (pinfunction "B_1") (pintype "passive"))
      (node (ref "R37") (pin "2") (pinfunction "2_2") (pintype "passive"))
      (node (ref "R38") (pin "1") (pinfunction "1_1") (pintype "passive"))
      (node (ref "R39") (pin "2") (pinfunction "2_2") (pintype "passive"))
    )
    (net (code "48") (name "Net-(Q9-C)") (class "Default")
      (node (ref "C26") (pin "2") (pinfunction "2_2") (pintype "passive"))
      (node (ref "INDUCTOR") (pin "-") (pinfunction "-_-") (pintype "passive"))
      (node (ref "Q9") (pin "3") (pinfunction "C_3") (pintype "passive"))
      (node (ref "R42") (pin "1") (pinfunction "1_1") (pintype "passive"))
      (node (ref "R43") (pin "1") (pinfunction "1_1") (pintype "passive"))
    )
    (net (code "49") (name "Net-(Q10-B)") (class "Default")
      (node (ref "C33") (pin "2") (pinfunction "2_2") (pintype "passive"))
      (node (ref "Q10") (pin "1") (pinfunction "B_1") (pintype "passive"))
      (node (ref "R47") (pin "1") (pinfunction "1_1") (pintype "passive"))
    )
    (net (code "50") (name "Net-(Q10-C)") (class "Default")
      (node (ref "C32") (pin "2") (pinfunction "2_2") (pintype "passive"))
      (node (ref "Q10") (pin "3") (pinfunction "C_3") (pintype "passive"))
      (node (ref "R47") (pin "2") (pinfunction "2_2") (pintype "passive"))
      (node (ref "R48") (pin "2") (pinfunction "2_2") (pintype "passive"))
      (node (ref "R49") (pin "1") (pinfunction "1_1") (pintype "passive"))
    )
    (net (code "51") (name "Net-(Q10-E)") (class "Default")
      (node (ref "Q10") (pin "2") (pinfunction "E_2") (pintype "passive"))
      (node (ref "VR14") (pin "1") (pinfunction "A_1") (pintype "passive"))
      (node (ref "VR14") (pin "2") (pinfunction "S_2") (pintype "passive"))
    )
    (net (code "52") (name "Net-(Q11-B)") (class "Default")
      (node (ref "Q11") (pin "1") (pinfunction "B_1") (pintype "passive"))
      (node (ref "R53") (pin "1") (pinfunction "1_1") (pintype "passive"))
      (node (ref "R54") (pin "2") (pinfunction "2_2") (pintype "passive"))
      (node (ref "R55") (pin "1") (pinfunction "1_1") (pintype "passive"))
    )
    (net (code "53") (name "Net-(Q11-C)") (class "Default")
      (node (ref "C37") (pin "2") (pinfunction "2_2") (pintype "passive"))
      (node (ref "Q11") (pin "3") (pinfunction "C_3") (pintype "passive"))
      (node (ref "R56") (pin "2") (pinfunction "2_2") (pintype "passive"))
      (node (ref "R57") (pin "1") (pinfunction "1_1") (pintype "passive"))
      (node (ref "R58") (pin "1") (pinfunction "1_1") (pintype "passive"))
    )
    (net (code "54") (name "Net-(Q12-B)") (class "Default")
      (node (ref "Q12") (pin "1") (pinfunction "B_1") (pintype "passive"))
      (node (ref "U8(CHH)") (pin "P$1_TIP") (pinfunction "TIP_P$1_TIP") (pintype "passive"))
    )
    (net (code "55") (name "Net-(Q12-C)") (class "Default")
      (node (ref "Q12") (pin "3") (pinfunction "C_3") (pintype "passive"))
      (node (ref "VR13") (pin "3") (pinfunction "E_3") (pintype "passive"))
    )
    (net (code "56") (name "Net-(Q12-E)") (class "Default")
      (node (ref "Q12") (pin "2") (pinfunction "E_2") (pintype "passive"))
      (node (ref "VR12") (pin "3") (pinfunction "E_3") (pintype "passive"))
    )
    (net (code "57") (name "Net-(U$2-IN)") (class "Default")
      (node (ref "C2") (pin "1") (pinfunction "1_1") (pintype "passive"))
      (node (ref "C46") (pin "+") (pinfunction "+_+") (pintype "passive"))
      (node (ref "D1") (pin "C") (pinfunction "C_C") (pintype "passive"))
      (node (ref "U$2") (pin "3") (pinfunction "IN_3") (pintype "input"))
    )
    (net (code "58") (name "Net-(U2-TIP)") (class "Default")
      (node (ref "D5") (pin "A") (pinfunction "A_A") (pintype "passive"))
      (node (ref "U2") (pin "P$1_TIP") (pinfunction "TIP_P$1_TIP") (pintype "passive"))
    )
    (net (code "59") (name "Net-(U3-TIP)") (class "Default")
      (node (ref "C19") (pin "-") (pinfunction "-_-") (pintype "passive"))
      (node (ref "R31") (pin "2") (pinfunction "2_2") (pintype "passive"))
      (node (ref "U3") (pin "P$1_TIP") (pinfunction "TIP_P$1_TIP") (pintype "passive"))
    )
    (net (code "60") (name "Net-(U4-TIP)") (class "Default")
      (node (ref "R6") (pin "1") (pinfunction "1_1") (pintype "passive"))
      (node (ref "U4") (pin "P$1_TIP") (pinfunction "TIP_P$1_TIP") (pintype "passive"))
    )
    (net (code "61") (name "Net-(U5-TIP)") (class "Default")
      (node (ref "C9") (pin "1") (pinfunction "1_1") (pintype "passive"))
      (node (ref "R13") (pin "2") (pinfunction "2_2") (pintype "passive"))
      (node (ref "U5") (pin "P$1_TIP") (pinfunction "TIP_P$1_TIP") (pintype "passive"))
    )
    (net (code "62") (name "Net-(U6(OHH)-TIP)") (class "Default")
      (node (ref "C28") (pin "1") (pinfunction "1_1") (pintype "passive"))
      (node (ref "U6(OHH)") (pin "P$1_TIP") (pinfunction "TIP_P$1_TIP") (pintype "passive"))
    )
    (net (code "63") (name "Net-(U7-TIP)") (class "Default")
      (node (ref "D6") (pin "A") (pinfunction "A_A") (pintype "passive"))
      (node (ref "R46") (pin "1") (pinfunction "1_1") (pintype "passive"))
      (node (ref "R50") (pin "2") (pinfunction "2_2") (pintype "passive"))
      (node (ref "U7") (pin "P$1_TIP") (pinfunction "TIP_P$1_TIP") (pintype "passive"))
    )
    (net (code "64") (name "Net-(U9-TIP)") (class "Default")
      (node (ref "U9") (pin "P$1_TIP") (pinfunction "TIP_P$1_TIP") (pintype "passive"))
      (node (ref "VR2") (pin "2") (pinfunction "S_2") (pintype "passive"))
    )
    (net (code "65") (name "Net-(U10-SWITCH)") (class "Default")
      (node (ref "U10") (pin "P$2_SWITCH") (pinfunction "SWITCH_P$2_SWITCH") (pintype "passive"))
      (node (ref "VR5") (pin "3") (pinfunction "E_3") (pintype "passive"))
    )
    (net (code "66") (name "Net-(U10-TIP)") (class "Default")
      (node (ref "C34") (pin "2") (pinfunction "2_2") (pintype "passive"))
      (node (ref "C38") (pin "2") (pinfunction "2_2") (pintype "passive"))
      (node (ref "U10") (pin "P$1_TIP") (pinfunction "TIP_P$1_TIP") (pintype "passive"))
    )
    (net (code "67") (name "Net-(U11-SWITCH)") (class "Default")
      (node (ref "C40") (pin "-") (pinfunction "-_-") (pintype "passive"))
      (node (ref "R21") (pin "1") (pinfunction "1_1") (pintype "passive"))
      (node (ref "U11") (pin "P$2_SWITCH") (pinfunction "SWITCH_P$2_SWITCH") (pintype "passive"))
      (node (ref "U12") (pin "P$2_SWITCH") (pinfunction "SWITCH_P$2_SWITCH") (pintype "passive"))
      (node (ref "U9") (pin "P$2_SWITCH") (pinfunction "SWITCH_P$2_SWITCH") (pintype "passive"))
      (node (ref "VR5") (pin "2") (pinfunction "S_2") (pintype "passive"))
    )
    (net (code "68") (name "Net-(U11-TIP)") (class "Default")
      (node (ref "U11") (pin "P$1_TIP") (pinfunction "TIP_P$1_TIP") (pintype "passive"))
      (node (ref "VR1") (pin "2") (pinfunction "S_2") (pintype "passive"))
    )
    (net (code "69") (name "Net-(U12-TIP)") (class "Default")
      (node (ref "U12") (pin "P$1_TIP") (pinfunction "TIP_P$1_TIP") (pintype "passive"))
      (node (ref "VR19") (pin "2") (pinfunction "S_2") (pintype "passive"))
    )
    (net (code "70") (name "Net-(VR1-E)") (class "Default")
      (node (ref "C8") (pin "2") (pinfunction "2_2") (pintype "passive"))
      (node (ref "VR1") (pin "3") (pinfunction "E_3") (pintype "passive"))
    )
    (net (code "71") (name "Net-(VR2-E)") (class "Default")
      (node (ref "C14") (pin "2") (pinfunction "2_2") (pintype "passive"))
      (node (ref "VR2") (pin "3") (pinfunction "E_3") (pintype "passive"))
    )
    (net (code "72") (name "Net-(VR3-S)") (class "Default")
      (node (ref "C40") (pin "+") (pinfunction "+_+") (pintype "passive"))
      (node (ref "R22") (pin "1") (pinfunction "1_1") (pintype "passive"))
      (node (ref "VR3") (pin "2") (pinfunction "S_2") (pintype "passive"))
    )
    (net (code "73") (name "Net-(VR4-CCW)") (class "Default")
      (node (ref "C20") (pin "+") (pinfunction "+_+") (pintype "passive"))
      (node (ref "R27") (pin "2") (pinfunction "2_2") (pintype "passive"))
      (node (ref "R32") (pin "1") (pinfunction "1_1") (pintype "passive"))
      (node (ref "VR4") (pin "1") (pinfunction "CCW_1") (pintype "passive"))
    )
    (net (code "74") (name "Net-(VR4-WIPER)") (class "Default")
      (node (ref "C15") (pin "+") (pinfunction "+_+") (pintype "passive"))
      (node (ref "R23") (pin "2") (pinfunction "2_2") (pintype "passive"))
      (node (ref "R24") (pin "2") (pinfunction "2_2") (pintype "passive"))
      (node (ref "VR4") (pin "2") (pinfunction "WIPER_2") (pintype "passive"))
    )
    (net (code "75") (name "Net-(VR6-S)") (class "Default")
      (node (ref "C22") (pin "1") (pinfunction "1_1") (pintype "passive"))
      (node (ref "VR6") (pin "2") (pinfunction "S_2") (pintype "passive"))
    )
    (net (code "76") (name "Net-(VR7-E)") (class "Default")
      (node (ref "C17") (pin "-") (pinfunction "-_-") (pintype "passive"))
      (node (ref "C30") (pin "2") (pinfunction "2_2") (pintype "passive"))
      (node (ref "C39") (pin "2") (pinfunction "2_2") (pintype "passive"))
      (node (ref "VR7") (pin "3") (pinfunction "E_3") (pintype "passive"))
    )
    (net (code "77") (name "Net-(VR7-S)") (class "Default")
      (node (ref "R29") (pin "2") (pinfunction "2_2") (pintype "passive"))
      (node (ref "VR7") (pin "2") (pinfunction "S_2") (pintype "passive"))
    )
    (net (code "78") (name "Net-(VR8-A)") (class "Default")
      (node (ref "C24") (pin "+") (pinfunction "+_+") (pintype "passive"))
      (node (ref "R34") (pin "1") (pinfunction "1_1") (pintype "passive"))
      (node (ref "R36") (pin "2") (pinfunction "2_2") (pintype "passive"))
      (node (ref "VR8") (pin "1") (pinfunction "A_1") (pintype "passive"))
    )
    (net (code "79") (name "Net-(VR8-S)") (class "Default")
      (node (ref "C25") (pin "1") (pinfunction "1_1") (pintype "passive"))
      (node (ref "C36") (pin "2") (pinfunction "2_2") (pintype "passive"))
      (node (ref "VR8") (pin "2") (pinfunction "S_2") (pintype "passive"))
    )
    (net (code "80") (name "Net-(VR9-E)") (class "Default")
      (node (ref "C1") (pin "1") (pinfunction "1_1") (pintype "passive"))
      (node (ref "C4") (pin "1") (pinfunction "1_1") (pintype "passive"))
      (node (ref "VR9") (pin "2") (pinfunction "S_2") (pintype "passive"))
      (node (ref "VR9") (pin "3") (pinfunction "E_3") (pintype "passive"))
    )
    (net (code "81") (name "Net-(VR10-E)") (class "Default")
      (node (ref "VR10") (pin "3") (pinfunction "E_3") (pintype "passive"))
      (node (ref "VR11") (pin "3") (pinfunction "CW_3") (pintype "passive"))
    )
    (net (code "82") (name "Net-(VR14-E)") (class "Default")
      (node (ref "VR14") (pin "3") (pinfunction "E_3") (pintype "passive"))
      (node (ref "VR15") (pin "3") (pinfunction "CW_3") (pintype "passive"))
    )
    (net (code "83") (name "Net-(VR16-E)") (class "Default")
      (node (ref "C31") (pin "2") (pinfunction "2_2") (pintype "passive"))
      (node (ref "C33") (pin "1") (pinfunction "1_1") (pintype "passive"))
      (node (ref "R46") (pin "2") (pinfunction "2_2") (pintype "passive"))
      (node (ref "VR16") (pin "2") (pinfunction "S_2") (pintype "passive"))
      (node (ref "VR16") (pin "3") (pinfunction "E_3") (pintype "passive"))
    )
    (net (code "84") (name "Net-(VR18-A)") (class "Default")
      (node (ref "C42") (pin "2") (pinfunction "2_2") (pintype "passive"))
      (node (ref "VR18") (pin "1") (pinfunction "A_1") (pintype "passive"))
      (node (ref "VR18") (pin "2") (pinfunction "S_2") (pintype "passive"))
    )
    (net (code "85") (name "Net-(VR19-E)") (class "Default")
      (node (ref "C29") (pin "2") (pinfunction "2_2") (pintype "passive"))
      (node (ref "VR19") (pin "3") (pinfunction "E_3") (pintype "passive"))
    )
    (net (code "86") (name "unconnected-(U2-SWITCH-PadP$2_SWITCH)") (class "Default")
      (node (ref "U2") (pin "P$2_SWITCH") (pinfunction "SWITCH_P$2_SWITCH") (pintype "passive"))
    )
    (net (code "87") (name "unconnected-(U3-SWITCH-PadP$2_SWITCH)") (class "Default")
      (node (ref "U3") (pin "P$2_SWITCH") (pinfunction "SWITCH_P$2_SWITCH") (pintype "passive"))
    )
    (net (code "88") (name "unconnected-(U4-SWITCH-PadP$2_SWITCH)") (class "Default")
      (node (ref "U4") (pin "P$2_SWITCH") (pinfunction "SWITCH_P$2_SWITCH") (pintype "passive"))
    )
    (net (code "89") (name "unconnected-(U5-SWITCH-PadP$2_SWITCH)") (class "Default")
      (node (ref "U5") (pin "P$2_SWITCH") (pinfunction "SWITCH_P$2_SWITCH") (pintype "passive"))
    )
    (net (code "90") (name "unconnected-(U6(OHH)-SWITCH-PadP$2_SWITCH)") (class "Default")
      (node (ref "U6(OHH)") (pin "P$2_SWITCH") (pinfunction "SWITCH_P$2_SWITCH") (pintype "passive"))
    )
    (net (code "91") (name "unconnected-(U7-SWITCH-PadP$2_SWITCH)") (class "Default")
      (node (ref "U7") (pin "P$2_SWITCH") (pinfunction "SWITCH_P$2_SWITCH") (pintype "passive"))
    )
    (net (code "92") (name "unconnected-(U8(CHH)-SWITCH-PadP$2_SWITCH)") (class "Default")
      (node (ref "U8(CHH)") (pin "P$2_SWITCH") (pinfunction "SWITCH_P$2_SWITCH") (pintype "passive"))
    )
    (net (code "93") (name "unconnected-(U13-Pad1)") (class "Default")
      (node (ref "U13") (pin "1") (pinfunction "1_1") (pintype "passive"))
    )
    (net (code "94") (name "unconnected-(U13-Pad9)") (class "Default")
      (node (ref "U13") (pin "9") (pinfunction "9_9") (pintype "passive"))
    )
    (net (code "95") (name "unconnected-(U13-Pad10)") (class "Default")
      (node (ref "U13") (pin "10") (pinfunction "10_10") (pintype "passive"))
    )
    (net (code "96") (name "unconnected-(VR3-E-Pad3)") (class "Default")
      (node (ref "VR3") (pin "3") (pinfunction "E_3") (pintype "passive"))
    )
    (net (code "97") (name "unconnected-(VR6-E-Pad3)") (class "Default")
      (node (ref "VR6") (pin "3") (pinfunction "E_3") (pintype "passive"))
    )
  )
)
